# CapModule.net
KiCad netlist of a schematic drawn in Altium Designer
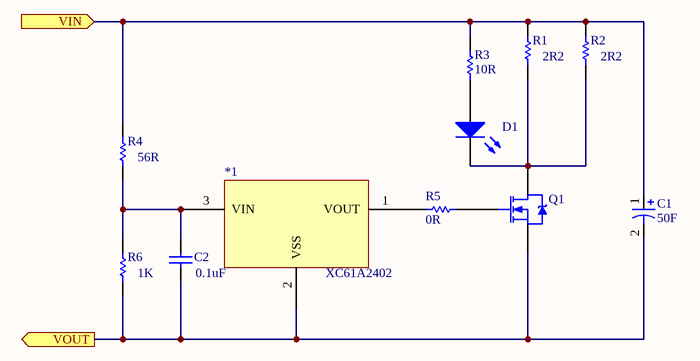
[diagram p0: CapModule.SchDoc]

(export (version "E")
  (design (tool "Eeschema 10.0.6"))
  (components
    (comp (ref "*1")
      (value "XC61A2402")
      (footprint "SOT23-3N")
      (libsource (lib "CapProtector") (part "XC61A"))
    )
    (comp (ref "C1")
      (value "50F")
      (footprint "CAP 7.5*18*35.5 - GD")
      (description "Polarized Capacitor (Radial) 2.7v")
      (fields (field (name "Comment") "Cap Pol1") (field (name "PUBLISHER") "Altium Limited"))
      (libsource (lib "Miscellaneous Devices") (part "Cap Pol1"))
    )
    (comp (ref "C2")
      (value "0.1uF")
      (footprint "0603C")
      (description "Capacitor")
      (fields (field (name "Comment") "Cap") (field (name "PUBLISHER") "Altium Limited"))
      (libsource (lib "Miscellaneous Devices") (part "Cap"))
    )
    (comp (ref "D1")
      (value "LED0")
      (footprint "LED 0603B")
      (description "Typical INFRARED GaAs LED")
      (fields (field (name "PUBLISHER") "Altium Limited"))
      (libsource (lib "Miscellaneous Devices") (part "LED0"))
    )
    (comp (ref "Q1")
      (value "NMOS-2")
      (footprint "sot23")
      (description "IRLML2502PbF")
      (fields (field (name "PUBLISHER") "Altium Limited"))
      (libsource (lib "Miscellaneous Devices") (part "NMOS-2"))
    )
    (comp (ref "R1")
      (value "2R2")
      (footprint "2512R")
      (description "Resistor")
      (fields (field (name "Comment") "Res1") (field (name "PUBLISHER") "Altium Limited"))
      (libsource (lib "Miscellaneous Devices") (part "Res1"))
    )
    (comp (ref "R2")
      (value "2R2")
      (footprint "2512R")
      (description "Resistor")
      (fields (field (name "Comment") "Res1") (field (name "PUBLISHER") "Altium Limited"))
      (libsource (lib "Miscellaneous Devices") (part "Res1"))
    )
    (comp (ref "R3")
      (value "10R")
      (footprint "0603R")
      (description "Resistor")
      (fields (field (name "Comment") "Res1") (field (name "PUBLISHER") "Altium Limited"))
      (libsource (lib "Miscellaneous Devices") (part "Res1"))
    )
    (comp (ref "R4")
      (value "56R")
      (footprint "0603R")
      (description "Resistor")
      (fields (field (name "Comment") "Res1") (field (name "PUBLISHER") "Altium Limited"))
      (libsource (lib "Miscellaneous Devices") (part "Res1"))
    )
    (comp (ref "R5")
      (value "0R")
      (footprint "0603R")
      (description "Resistor")
      (fields (field (name "Comment") "Res1") (field (name "PUBLISHER") "Altium Limited"))
      (libsource (lib "Miscellaneous Devices") (part "Res1"))
    )
    (comp (ref "R6")
      (value "1K")
      (footprint "0603R")
      (description "Resistor")
      (fields (field (name "Comment") "Res1") (field (name "PUBLISHER") "Altium Limited"))
      (libsource (lib "Miscellaneous Devices") (part "Res1"))
    )
  )
  (nets
    (net (code "1") (name "/VIN") (class "Default")
      (node (ref "C1") (pin "1") (pinfunction "1_1") (pintype "passive"))
      (node (ref "R1") (pin "2") (pinfunction "2_2") (pintype "passive"))
      (node (ref "R2") (pin "2") (pinfunction "2_2") (pintype "passive"))
      (node (ref "R3") (pin "1") (pinfunction "1_1") (pintype "passive"))
      (node (ref "R4") (pin "2") (pinfunction "2_2") (pintype "passive"))
    )
    (net (code "2") (name "/VOUT") (class "Default")
      (node (ref "*1") (pin "2") (pinfunction "VSS_2") (pintype "passive"))
      (node (ref "C1") (pin "2") (pinfunction "2_2") (pintype "passive"))
      (node (ref "C2") (pin "1") (pinfunction "1_1") (pintype "passive"))
      (node (ref "Q1") (pin "3") (pinfunction "S_3") (pintype "passive"))
      (node (ref "R6") (pin "1") (pinfunction "1_1") (pintype "passive"))
    )
    (net (code "3") (name "Net-(*1-VIN)") (class "Default")
      (node (ref "*1") (pin "3") (pinfunction "VIN_3") (pintype "passive"))
      (node (ref "C2") (pin "2") (pinfunction "2_2") (pintype "passive"))
      (node (ref "R4") (pin "1") (pinfunction "1_1") (pintype "passive"))
      (node (ref "R6") (pin "2") (pinfunction "2_2") (pintype "passive"))
    )
    (net (code "4") (name "Net-(*1-VOUT)") (class "Default")
      (node (ref "*1") (pin "1") (pinfunction "VOUT_1") (pintype "passive"))
      (node (ref "R5") (pin "2") (pinfunction "2_2") (pintype "passive"))
    )
    (net (code "5") (name "Net-(D1-A)") (class "Default")
      (node (ref "D1") (pin "1") (pinfunction "A_1") (pintype "passive"))
      (node (ref "R3") (pin "2") (pinfunction "2_2") (pintype "passive"))
    )
    (net (code "6") (name "Net-(D1-K)") (class "Default")
      (node (ref "D1") (pin "2") (pinfunction "K_2") (pintype "passive"))
      (node (ref "Q1") (pin "2") (pinfunction "D_2") (pintype "passive"))
      (node (ref "R1") (pin "1") (pinfunction "1_1") (pintype "passive"))
      (node (ref "R2") (pin "1") (pinfunction "1_1") (pintype "passive"))
    )
    (net (code "7") (name "Net-(Q1-G)") (class "Default")
      (node (ref "Q1") (pin "1") (pinfunction "G_1") (pintype "passive"))
      (node (ref "R5") (pin "1") (pinfunction "1_1") (pintype "passive"))
    )
  )
)
